# MotorController.net
KiCad netlist of a schematic drawn in Altium Designer
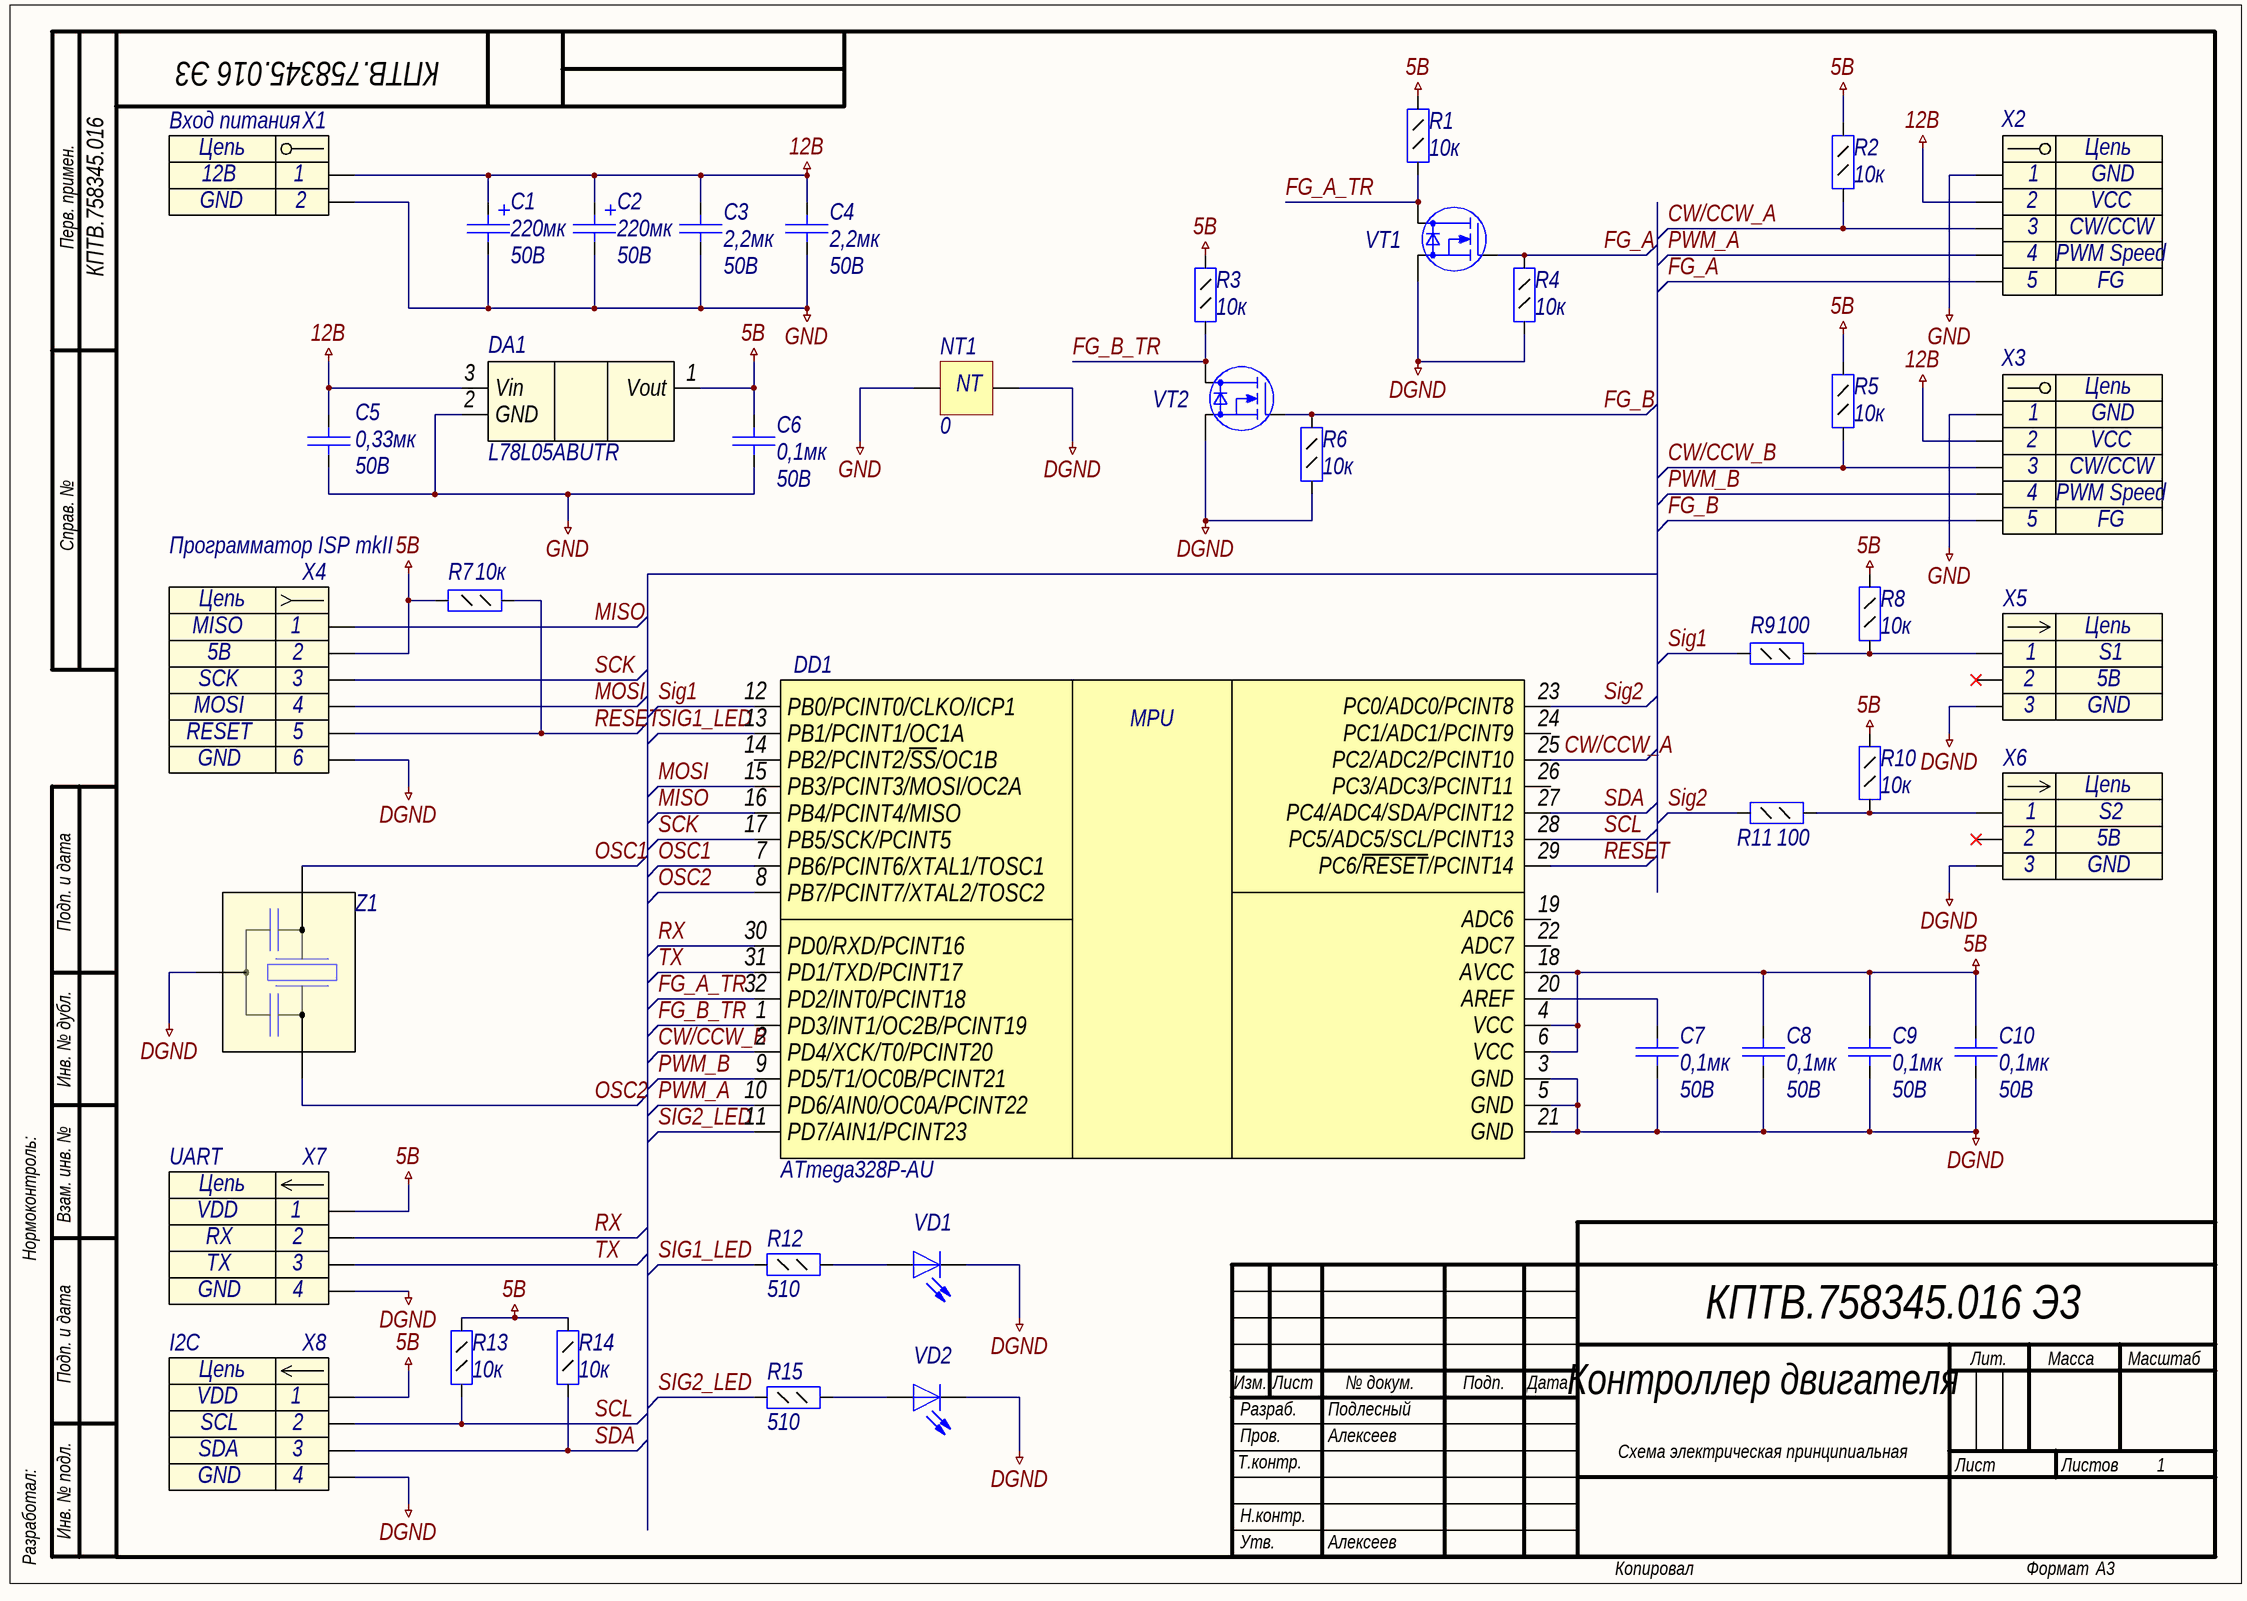
[diagram p0: MotorController.schdoc]

(export (version "E")
  (design (tool "Eeschema 10.0.6"))
  (components
    (comp (ref "C1")
      (value "220мк")
      (footprint "Cap_SMD_radial_polar(10x10.5)")
      (description "Конденсатор полярный")
      (fields
        (field (name "VOLTAGE") "50В")
        (field (name "PART NUMBER") "ECAP SMD")
        (field (name "Comment") "Capacitor_pol")
      )
      (libsource (lib "MOP44") (part "Capacitor_pol"))
    )
    (comp (ref "C2")
      (value "220мк")
      (footprint "Cap_SMD_radial_polar(10x10.5)")
      (description "Конденсатор полярный")
      (fields
        (field (name "VOLTAGE") "50В")
        (field (name "PART NUMBER") "ECAP SMD")
        (field (name "Comment") "Capacitor_pol")
      )
      (libsource (lib "MOP44") (part "Capacitor_pol"))
    )
    (comp (ref "C3")
      (value "2,2мк")
      (footprint "C1206")
      (description "Конденсатор")
      (fields
        (field (name "VOLTAGE") "50В")
        (field (name "PART NUMBER") "GRM31CR71H225KA88**L")
        (field (name "Comment") "Capacitor")
      )
      (libsource (lib "MOP44") (part "Capacitor"))
    )
    (comp (ref "C4")
      (value "2,2мк")
      (footprint "C1206")
      (description "Конденсатор")
      (fields
        (field (name "VOLTAGE") "50В")
        (field (name "PART NUMBER") "GRM31CR71H225KA88**L")
        (field (name "Comment") "Capacitor")
      )
      (libsource (lib "MOP44") (part "Capacitor"))
    )
    (comp (ref "C5")
      (value "0,33мк")
      (footprint "C1206")
      (description "Конденсатор")
      (fields
        (field (name "VOLTAGE") "50В")
        (field (name "PART NUMBER") "GRM319R71H334K")
        (field (name "Comment") "Capacitor")
      )
      (libsource (lib "MOP44") (part "Capacitor"))
    )
    (comp (ref "C6")
      (value "0,1мк")
      (footprint "C0805")
      (description "Конденсатор")
      (fields
        (field (name "VOLTAGE") "50В")
        (field (name "PART NUMBER") "GRM21BR71H104KA01L ")
        (field (name "Comment") "Capacitor")
      )
      (libsource (lib "MOP44") (part "Capacitor"))
    )
    (comp (ref "C7")
      (value "0,1мк")
      (footprint "C0805")
      (description "Конденсатор")
      (fields
        (field (name "VOLTAGE") "50В")
        (field (name "PART NUMBER") "GRM21BR71H104KA01L ")
        (field (name "Comment") "Capacitor")
      )
      (libsource (lib "MOP44") (part "Capacitor"))
    )
    (comp (ref "C8")
      (value "0,1мк")
      (footprint "C0805")
      (description "Конденсатор")
      (fields
        (field (name "VOLTAGE") "50В")
        (field (name "PART NUMBER") "GRM21BR71H104KA01L ")
        (field (name "Comment") "Capacitor")
      )
      (libsource (lib "MOP44") (part "Capacitor"))
    )
    (comp (ref "C9")
      (value "0,1мк")
      (footprint "C0805")
      (description "Конденсатор")
      (fields
        (field (name "VOLTAGE") "50В")
        (field (name "PART NUMBER") "GRM21BR71H104KA01L ")
        (field (name "Comment") "Capacitor")
      )
      (libsource (lib "MOP44") (part "Capacitor"))
    )
    (comp (ref "C10")
      (value "0,1мк")
      (footprint "C0805")
      (description "Конденсатор")
      (fields
        (field (name "VOLTAGE") "50В")
        (field (name "PART NUMBER") "GRM21BR71H104KA01L ")
        (field (name "Comment") "Capacitor")
      )
      (libsource (lib "MOP44") (part "Capacitor"))
    )
    (comp (ref "DA1")
      (value "L78L05ABUTR")
      (footprint "SOT-89-3")
      (description "Cтабилизатор напряжения (+5В; 0.1А), 4%, (-40...+125C)")
      (fields (field (name "MANUFACTURER") "ST Microelectronics"))
      (libsource (lib "MOP44") (part "L78L05ABUTR"))
    )
    (comp (ref "DD1")
      (value "ATmega328P-AU")
      (footprint "TQFP-32")
      (description "Микроконтроллер 8-Бит, picoPower, AVR, 20МГц, 32КБ Flash")
      (libsource (lib "MOP44") (part "ATmega328P-AU"))
    )
    (comp (ref "NT1") (value "0") (footprint "Pofigistor0603") (libsource (lib "MOP44") (part "Pofigistor")))
    (comp (ref "R1")
      (value "10к")
      (footprint "R0805")
      (description "Резистор")
      (fields (field (name "POWER") "0,125Вт") (field (name "Comment") "Resistor_0,125Вт"))
      (libsource (lib "MOP44") (part "Resistor_0,125Вт"))
    )
    (comp (ref "R2")
      (value "10к")
      (footprint "R0805")
      (description "Резистор")
      (fields (field (name "POWER") "0,125Вт") (field (name "Comment") "Resistor_0,125Вт"))
      (libsource (lib "MOP44") (part "Resistor_0,125Вт"))
    )
    (comp (ref "R3")
      (value "10к")
      (footprint "R0805")
      (description "Резистор")
      (fields (field (name "POWER") "0,125Вт") (field (name "Comment") "Resistor_0,125Вт"))
      (libsource (lib "MOP44") (part "Resistor_0,125Вт"))
    )
    (comp (ref "R4")
      (value "10к")
      (footprint "R0805")
      (description "Резистор")
      (fields (field (name "POWER") "0,125Вт") (field (name "Comment") "Resistor_0,125Вт"))
      (libsource (lib "MOP44") (part "Resistor_0,125Вт"))
    )
    (comp (ref "R5")
      (value "10к")
      (footprint "R0805")
      (description "Резистор")
      (fields (field (name "POWER") "0,125Вт") (field (name "Comment") "Resistor_0,125Вт"))
      (libsource (lib "MOP44") (part "Resistor_0,125Вт"))
    )
    (comp (ref "R6")
      (value "10к")
      (footprint "R0805")
      (description "Резистор")
      (fields (field (name "POWER") "0,125Вт") (field (name "Comment") "Resistor_0,125Вт"))
      (libsource (lib "MOP44") (part "Resistor_0,125Вт"))
    )
    (comp (ref "R7")
      (value "10к")
      (footprint "R0805")
      (description "Резистор")
      (fields (field (name "POWER") "0,125Вт") (field (name "Comment") "Resistor_0,125Вт"))
      (libsource (lib "") (part "Resistor_0,125Вт_1"))
    )
    (comp (ref "R8")
      (value "10к")
      (footprint "R0805")
      (description "Резистор")
      (fields (field (name "POWER") "0,125Вт") (field (name "Comment") "Resistor_0,125Вт"))
      (libsource (lib "MOP44") (part "Resistor_0,125Вт"))
    )
    (comp (ref "R9")
      (value "100")
      (footprint "R0805")
      (description "Резистор")
      (fields (field (name "POWER") "0,125Вт") (field (name "Comment") "Resistor_0,125Вт"))
      (libsource (lib "") (part "Resistor_0,125Вт_2"))
    )
    (comp (ref "R10")
      (value "10к")
      (footprint "R0805")
      (description "Резистор")
      (fields (field (name "POWER") "0,125Вт") (field (name "Comment") "Resistor_0,125Вт"))
      (libsource (lib "MOP44") (part "Resistor_0,125Вт"))
    )
    (comp (ref "R11")
      (value "100")
      (footprint "R0805")
      (description "Резистор")
      (fields (field (name "POWER") "0,125Вт") (field (name "Comment") "Resistor_0,125Вт"))
      (libsource (lib "") (part "Resistor_0,125Вт_2"))
    )
    (comp (ref "R12")
      (value "510")
      (footprint "R0805")
      (description "Резистор")
      (fields (field (name "PART NUMBER") "RC0805FR-07510RL") (field (name "POWER") "0,125Вт"))
      (libsource (lib "") (part "Resistor_0,125Вт_2"))
    )
    (comp (ref "R13")
      (value "10к")
      (footprint "R0805")
      (description "Резистор")
      (fields (field (name "POWER") "0,125Вт") (field (name "Comment") "Resistor_0,125Вт"))
      (libsource (lib "MOP44") (part "Resistor_0,125Вт"))
    )
    (comp (ref "R14")
      (value "10к")
      (footprint "R0805")
      (description "Резистор")
      (fields (field (name "POWER") "0,125Вт") (field (name "Comment") "Resistor_0,125Вт"))
      (libsource (lib "MOP44") (part "Resistor_0,125Вт"))
    )
    (comp (ref "R15")
      (value "510")
      (footprint "R0805")
      (description "Резистор")
      (fields (field (name "PART NUMBER") "RC0805FR-07510RL") (field (name "POWER") "0,125Вт"))
      (libsource (lib "") (part "Resistor_0,125Вт_2"))
    )
    (comp (ref "VD1")
      (value "LED")
      (footprint "L_0805")
      (description "Светодиод")
      (fields (field (name "PART NUMBER") "KP-2012EC"))
      (libsource (lib "MOP44") (part "LED"))
    )
    (comp (ref "VD2")
      (value "LED")
      (footprint "L_0805")
      (description "Светодиод")
      (fields (field (name "PART NUMBER") "KP-2012EC"))
      (libsource (lib "MOP44") (part "LED"))
    )
    (comp (ref "VT1")
      (value "N-MOSFET")
      (footprint "SOT23-3")
      (fields
        (field (name "PART NUMBER") "IRLML2402TRPBF")
        (field (name "MANUFACTURER") "International Rectifier")
      )
      (libsource (lib "MOP44") (part "N-MOSFET"))
    )
    (comp (ref "VT2")
      (value "N-MOSFET")
      (footprint "SOT23-3")
      (fields
        (field (name "PART NUMBER") "IRLML2402TRPBF")
        (field (name "MANUFACTURER") "International Rectifier")
      )
      (libsource (lib "MOP44") (part "N-MOSFET"))
    )
    (comp (ref "X1")
      (value "Вход питания")
      (footprint "TERMINAL-2WAY-3.5MM")
      (description "Разъем - 2 конт. клеммник")
      (libsource (lib "MOP44") (part "Header_2_trm"))
    )
    (comp (ref "X2")
      (value "Header_5_trm")
      (footprint "TERMINAL-5WAY-3.5MM_")
      (description "Разъем - 5 конт. клеммник")
      (libsource (lib "MOP44") (part "Header_5_trm"))
    )
    (comp (ref "X3")
      (value "Управление двигателем B")
      (footprint "TERMINAL-5WAY-3.5MM")
      (description "Разъем - 5 конт. клеммник")
      (libsource (lib "MOP44") (part "Header_5_trm"))
    )
    (comp (ref "X4")
      (value "Программатор ISP mkII")
      (footprint "PLS2-6")
      (description "Разъем - 6 конт. розетка")
      (libsource (lib "MOP44") (part "Header_6_sct"))
    )
    (comp (ref "X5")
      (value "Header_3_plg")
      (footprint "PLS-3")
      (description "Разъем - 3 конт. вилка")
      (fields (field (name "PART NUMBER") "DS1021-1*3SF112-B"))
      (libsource (lib "MOP44") (part "Header_3_plg"))
    )
    (comp (ref "X6")
      (value "Header_3_plg")
      (footprint "PLS-3")
      (description "Разъем - 3 конт. вилка")
      (fields (field (name "PART NUMBER") "DS1021-1*3SF112-B"))
      (libsource (lib "MOP44") (part "Header_3_plg"))
    )
    (comp (ref "X7")
      (value "UART")
      (footprint "PLS-4")
      (description "Разъем - 4 конт. вилка")
      (fields (field (name "PART NUMBER") "DS1021-1*4SF112-B"))
      (libsource (lib "MOP44") (part "Header_4_plg"))
    )
    (comp (ref "X8")
      (value "I2C")
      (footprint "PLS-4")
      (description "Разъем - 4 конт. вилка")
      (fields (field (name "PART NUMBER") "DS1021-1*4SF112-B"))
      (libsource (lib "MOP44") (part "Header_4_plg"))
    )
    (comp (ref "Z1")
      (value "QuartzWithCaps")
      (footprint "CSTCE")
      (description "Кварцевый резорнатор со встроенными нагрузочными конденсаторами")
      (fields (field (name "PART NUMBER") "CSTCE12M0G52-R0"))
      (libsource (lib "MOP44") (part "QuartzWithCaps"))
    )
  )
  (nets
    (net (code "1") (name "/CW{slash}CCW_A") (class "Default")
      (node (ref "DD1") (pin "25") (pinfunction "PC2/ADC2/PCINT10_25") (pintype "passive"))
      (node (ref "R2") (pin "2") (pinfunction "2_2") (pintype "passive"))
      (node (ref "X2") (pin "3") (pinfunction "3_3") (pintype "passive"))
    )
    (net (code "2") (name "/CW{slash}CCW_B") (class "Default")
      (node (ref "DD1") (pin "2") (pinfunction "PD4/XCK/T0/PCINT20_2") (pintype "passive"))
      (node (ref "R5") (pin "2") (pinfunction "2_2") (pintype "passive"))
      (node (ref "X3") (pin "3") (pinfunction "3_3") (pintype "passive"))
    )
    (net (code "3") (name "/FG_A") (class "Default")
      (node (ref "R4") (pin "1") (pinfunction "1_1") (pintype "passive"))
      (node (ref "VT1") (pin "1") (pinfunction "G_1") (pintype "passive"))
      (node (ref "X2") (pin "5") (pinfunction "5_5") (pintype "passive"))
    )
    (net (code "4") (name "/FG_A_TR") (class "Default")
      (node (ref "DD1") (pin "32") (pinfunction "PD2/INT0/PCINT18_32") (pintype "passive"))
      (node (ref "R1") (pin "2") (pinfunction "2_2") (pintype "passive"))
      (node (ref "VT1") (pin "2") (pinfunction "D_2") (pintype "passive"))
    )
    (net (code "5") (name "/FG_B") (class "Default")
      (node (ref "R6") (pin "1") (pinfunction "1_1") (pintype "passive"))
      (node (ref "VT2") (pin "1") (pinfunction "G_1") (pintype "passive"))
      (node (ref "X3") (pin "5") (pinfunction "5_5") (pintype "passive"))
    )
    (net (code "6") (name "/FG_B_TR") (class "Default")
      (node (ref "DD1") (pin "1") (pinfunction "PD3/INT1/OC2B/PCINT19_1") (pintype "passive"))
      (node (ref "R3") (pin "2") (pinfunction "2_2") (pintype "passive"))
      (node (ref "VT2") (pin "2") (pinfunction "D_2") (pintype "passive"))
    )
    (net (code "7") (name "/MISO") (class "Default")
      (node (ref "DD1") (pin "16") (pinfunction "PB4/PCINT4/MISO_16") (pintype "passive"))
      (node (ref "X4") (pin "1") (pinfunction "1_1") (pintype "passive"))
    )
    (net (code "8") (name "/MOSI") (class "Default")
      (node (ref "DD1") (pin "15") (pinfunction "PB3/PCINT3/MOSI/OC2A_15") (pintype "passive"))
      (node (ref "X4") (pin "4") (pinfunction "4_4") (pintype "passive"))
    )
    (net (code "9") (name "/OSC1") (class "Default")
      (node (ref "DD1") (pin "7") (pinfunction "PB6/PCINT6/XTAL1/TOSC1_7") (pintype "passive"))
      (node (ref "Z1") (pin "3") (pinfunction "3_3") (pintype "passive"))
    )
    (net (code "10") (name "/OSC2") (class "Default")
      (node (ref "DD1") (pin "8") (pinfunction "PB7/PCINT7/XTAL2/TOSC2_8") (pintype "passive"))
      (node (ref "Z1") (pin "1") (pinfunction "1_1") (pintype "passive"))
    )
    (net (code "11") (name "/PWM_A") (class "Default")
      (node (ref "DD1") (pin "10") (pinfunction "PD6/AIN0/OC0A/PCINT22_10") (pintype "passive"))
      (node (ref "X2") (pin "4") (pinfunction "4_4") (pintype "passive"))
    )
    (net (code "12") (name "/PWM_B") (class "Default")
      (node (ref "DD1") (pin "9") (pinfunction "PD5/T1/OC0B/PCINT21_9") (pintype "passive"))
      (node (ref "X3") (pin "4") (pinfunction "4_4") (pintype "passive"))
    )
    (net (code "13") (name "/RESET") (class "Default")
      (node (ref "DD1") (pin "29") (pinfunction "PC6/~{RESET}/PCINT14_29") (pintype "passive"))
      (node (ref "R7") (pin "1") (pinfunction "1_1") (pintype "passive"))
      (node (ref "X4") (pin "5") (pinfunction "5_5") (pintype "passive"))
    )
    (net (code "14") (name "/RX") (class "Default")
      (node (ref "DD1") (pin "30") (pinfunction "PD0/RXD/PCINT16_30") (pintype "passive"))
      (node (ref "X7") (pin "2") (pinfunction "2_2") (pintype "passive"))
    )
    (net (code "15") (name "/SCK") (class "Default")
      (node (ref "DD1") (pin "17") (pinfunction "PB5/SCK/PCINT5_17") (pintype "passive"))
      (node (ref "X4") (pin "3") (pinfunction "3_3") (pintype "passive"))
    )
    (net (code "16") (name "/SCL") (class "Default")
      (node (ref "DD1") (pin "28") (pinfunction "PC5/ADC5/SCL/PCINT13_28") (pintype "passive"))
      (node (ref "R13") (pin "2") (pinfunction "2_2") (pintype "passive"))
      (node (ref "X8") (pin "2") (pinfunction "2_2") (pintype "passive"))
    )
    (net (code "17") (name "/SDA") (class "Default")
      (node (ref "DD1") (pin "27") (pinfunction "PC4/ADC4/SDA/PCINT12_27") (pintype "passive"))
      (node (ref "R14") (pin "2") (pinfunction "2_2") (pintype "passive"))
      (node (ref "X8") (pin "3") (pinfunction "3_3") (pintype "passive"))
    )
    (net (code "18") (name "/SIG1_LED") (class "Default")
      (node (ref "DD1") (pin "13") (pinfunction "PB1/PCINT1/OC1A_13") (pintype "passive"))
      (node (ref "R12") (pin "1") (pinfunction "1_1") (pintype "passive"))
    )
    (net (code "19") (name "/SIG2_LED") (class "Default")
      (node (ref "DD1") (pin "11") (pinfunction "PD7/AIN1/PCINT23_11") (pintype "passive"))
      (node (ref "R15") (pin "1") (pinfunction "1_1") (pintype "passive"))
    )
    (net (code "20") (name "/Sig1") (class "Default")
      (node (ref "DD1") (pin "12") (pinfunction "PB0/PCINT0/CLKO/ICP1_12") (pintype "passive"))
      (node (ref "R9") (pin "1") (pinfunction "1_1") (pintype "passive"))
    )
    (net (code "21") (name "/Sig2") (class "Default")
      (node (ref "DD1") (pin "23") (pinfunction "PC0/ADC0/PCINT8_23") (pintype "passive"))
      (node (ref "R11") (pin "1") (pinfunction "1_1") (pintype "passive"))
    )
    (net (code "22") (name "/TX") (class "Default")
      (node (ref "DD1") (pin "31") (pinfunction "PD1/TXD/PCINT17_31") (pintype "passive"))
      (node (ref "X7") (pin "3") (pinfunction "3_3") (pintype "passive"))
    )
    (net (code "23") (name "5B") (class "Default")
      (node (ref "C10") (pin "2") (pinfunction "2_2") (pintype "passive"))
      (node (ref "C6") (pin "2") (pinfunction "2_2") (pintype "passive"))
      (node (ref "C8") (pin "2") (pinfunction "2_2") (pintype "passive"))
      (node (ref "C9") (pin "2") (pinfunction "2_2") (pintype "passive"))
      (node (ref "DA1") (pin "1") (pinfunction "Vout_1") (pintype "power_in"))
      (node (ref "DD1") (pin "18") (pinfunction "AVCC_18") (pintype "passive"))
      (node (ref "DD1") (pin "4") (pinfunction "VCC_4") (pintype "passive"))
      (node (ref "DD1") (pin "6") (pinfunction "VCC_6") (pintype "passive"))
      (node (ref "R1") (pin "1") (pinfunction "1_1") (pintype "passive"))
      (node (ref "R10") (pin "1") (pinfunction "1_1") (pintype "passive"))
      (node (ref "R13") (pin "1") (pinfunction "1_1") (pintype "passive"))
      (node (ref "R14") (pin "1") (pinfunction "1_1") (pintype "passive"))
      (node (ref "R2") (pin "1") (pinfunction "1_1") (pintype "passive"))
      (node (ref "R3") (pin "1") (pinfunction "1_1") (pintype "passive"))
      (node (ref "R5") (pin "1") (pinfunction "1_1") (pintype "passive"))
      (node (ref "R7") (pin "2") (pinfunction "2_2") (pintype "passive"))
      (node (ref "R8") (pin "1") (pinfunction "1_1") (pintype "passive"))
      (node (ref "X4") (pin "2") (pinfunction "2_2") (pintype "passive"))
      (node (ref "X7") (pin "1") (pinfunction "1_1") (pintype "passive"))
      (node (ref "X8") (pin "1") (pinfunction "1_1") (pintype "passive"))
    )
    (net (code "24") (name "12B") (class "Default")
      (node (ref "C1") (pin "1") (pinfunction "1_1") (pintype "passive"))
      (node (ref "C2") (pin "1") (pinfunction "1_1") (pintype "passive"))
      (node (ref "C3") (pin "2") (pinfunction "2_2") (pintype "passive"))
      (node (ref "C4") (pin "2") (pinfunction "2_2") (pintype "passive"))
      (node (ref "C5") (pin "2") (pinfunction "2_2") (pintype "passive"))
      (node (ref "DA1") (pin "3") (pinfunction "Vin_3") (pintype "power_in"))
      (node (ref "X1") (pin "1") (pinfunction "1_1") (pintype "passive"))
      (node (ref "X2") (pin "2") (pinfunction "2_2") (pintype "passive"))
      (node (ref "X3") (pin "2") (pinfunction "2_2") (pintype "passive"))
    )
    (net (code "25") (name "DGND") (class "Default")
      (node (ref "C10") (pin "1") (pinfunction "1_1") (pintype "passive"))
      (node (ref "C7") (pin "1") (pinfunction "1_1") (pintype "passive"))
      (node (ref "C8") (pin "1") (pinfunction "1_1") (pintype "passive"))
      (node (ref "C9") (pin "1") (pinfunction "1_1") (pintype "passive"))
      (node (ref "DD1") (pin "21") (pinfunction "GND_21") (pintype "passive"))
      (node (ref "DD1") (pin "3") (pinfunction "GND_3") (pintype "passive"))
      (node (ref "DD1") (pin "5") (pinfunction "GND_5") (pintype "passive"))
      (node (ref "NT1") (pin "2") (pinfunction "2_2") (pintype "passive"))
      (node (ref "R4") (pin "2") (pinfunction "2_2") (pintype "passive"))
      (node (ref "R6") (pin "2") (pinfunction "2_2") (pintype "passive"))
      (node (ref "VD1") (pin "1") (pinfunction "K_1") (pintype "passive"))
      (node (ref "VD2") (pin "1") (pinfunction "K_1") (pintype "passive"))
      (node (ref "VT1") (pin "3") (pinfunction "S_3") (pintype "passive"))
      (node (ref "VT2") (pin "3") (pinfunction "S_3") (pintype "passive"))
      (node (ref "X4") (pin "6") (pinfunction "6_6") (pintype "passive"))
      (node (ref "X5") (pin "3") (pinfunction "3_3") (pintype "passive"))
      (node (ref "X6") (pin "3") (pinfunction "3_3") (pintype "passive"))
      (node (ref "X7") (pin "4") (pinfunction "4_4") (pintype "passive"))
      (node (ref "X8") (pin "4") (pinfunction "4_4") (pintype "passive"))
      (node (ref "Z1") (pin "2") (pinfunction "2_2") (pintype "passive"))
    )
    (net (code "26") (name "GND") (class "Default")
      (node (ref "C1") (pin "2") (pinfunction "2_2") (pintype "passive"))
      (node (ref "C2") (pin "2") (pinfunction "2_2") (pintype "passive"))
      (node (ref "C3") (pin "1") (pinfunction "1_1") (pintype "passive"))
      (node (ref "C4") (pin "1") (pinfunction "1_1") (pintype "passive"))
      (node (ref "C5") (pin "1") (pinfunction "1_1") (pintype "passive"))
      (node (ref "C6") (pin "1") (pinfunction "1_1") (pintype "passive"))
      (node (ref "DA1") (pin "2") (pinfunction "GND_2") (pintype "power_in"))
      (node (ref "NT1") (pin "1") (pinfunction "1_1") (pintype "passive"))
      (node (ref "X1") (pin "2") (pinfunction "2_2") (pintype "passive"))
      (node (ref "X2") (pin "1") (pinfunction "1_1") (pintype "passive"))
      (node (ref "X3") (pin "1") (pinfunction "1_1") (pintype "passive"))
    )
    (net (code "27") (name "Net-(DD1-AREF)") (class "Default")
      (node (ref "C7") (pin "2") (pinfunction "2_2") (pintype "passive"))
      (node (ref "DD1") (pin "20") (pinfunction "AREF_20") (pintype "passive"))
    )
    (net (code "28") (name "Net-(R8-Pad2)") (class "Default")
      (node (ref "R8") (pin "2") (pinfunction "2_2") (pintype "passive"))
      (node (ref "R9") (pin "2") (pinfunction "2_2") (pintype "passive"))
      (node (ref "X5") (pin "1") (pinfunction "1_1") (pintype "passive"))
    )
    (net (code "29") (name "Net-(R10-Pad2)") (class "Default")
      (node (ref "R10") (pin "2") (pinfunction "2_2") (pintype "passive"))
      (node (ref "R11") (pin "2") (pinfunction "2_2") (pintype "passive"))
      (node (ref "X6") (pin "1") (pinfunction "1_1") (pintype "passive"))
    )
    (net (code "30") (name "Net-(VD1-A)") (class "Default")
      (node (ref "R12") (pin "2") (pinfunction "2_2") (pintype "passive"))
      (node (ref "VD1") (pin "2") (pinfunction "A_2") (pintype "passive"))
    )
    (net (code "31") (name "Net-(VD2-A)") (class "Default")
      (node (ref "R15") (pin "2") (pinfunction "2_2") (pintype "passive"))
      (node (ref "VD2") (pin "2") (pinfunction "A_2") (pintype "passive"))
    )
    (net (code "32") (name "unconnected-(DD1-ADC6-Pad19)") (class "Default")
      (node (ref "DD1") (pin "19") (pinfunction "ADC6_19") (pintype "passive"))
    )
    (net (code "33") (name "unconnected-(DD1-ADC7-Pad22)") (class "Default")
      (node (ref "DD1") (pin "22") (pinfunction "ADC7_22") (pintype "passive"))
    )
    (net (code "34") (name "unconnected-(DD1-PB2{slash}PCINT2{slash}~{SS}{slash}OC1B-Pad14)") (class "Default")
      (node (ref "DD1") (pin "14") (pinfunction "PB2/PCINT2/~{SS}/OC1B_14") (pintype "passive"))
    )
    (net (code "35") (name "unconnected-(DD1-PC1{slash}ADC1{slash}PCINT9-Pad24)") (class "Default")
      (node (ref "DD1") (pin "24") (pinfunction "PC1/ADC1/PCINT9_24") (pintype "passive"))
    )
    (net (code "36") (name "unconnected-(DD1-PC3{slash}ADC3{slash}PCINT11-Pad26)") (class "Default")
      (node (ref "DD1") (pin "26") (pinfunction "PC3/ADC3/PCINT11_26") (pintype "passive"))
    )
    (net (code "37") (name "unconnected-(X5-Pad2)") (class "Default")
      (node (ref "X5") (pin "2") (pinfunction "2_2") (pintype "passive+no_connect"))
    )
    (net (code "38") (name "unconnected-(X6-Pad2)") (class "Default")
      (node (ref "X6") (pin "2") (pinfunction "2_2") (pintype "passive+no_connect"))
    )
  )
)
